# pr0board_key.net
KiCad netlist of a schematic drawn in EAGLE
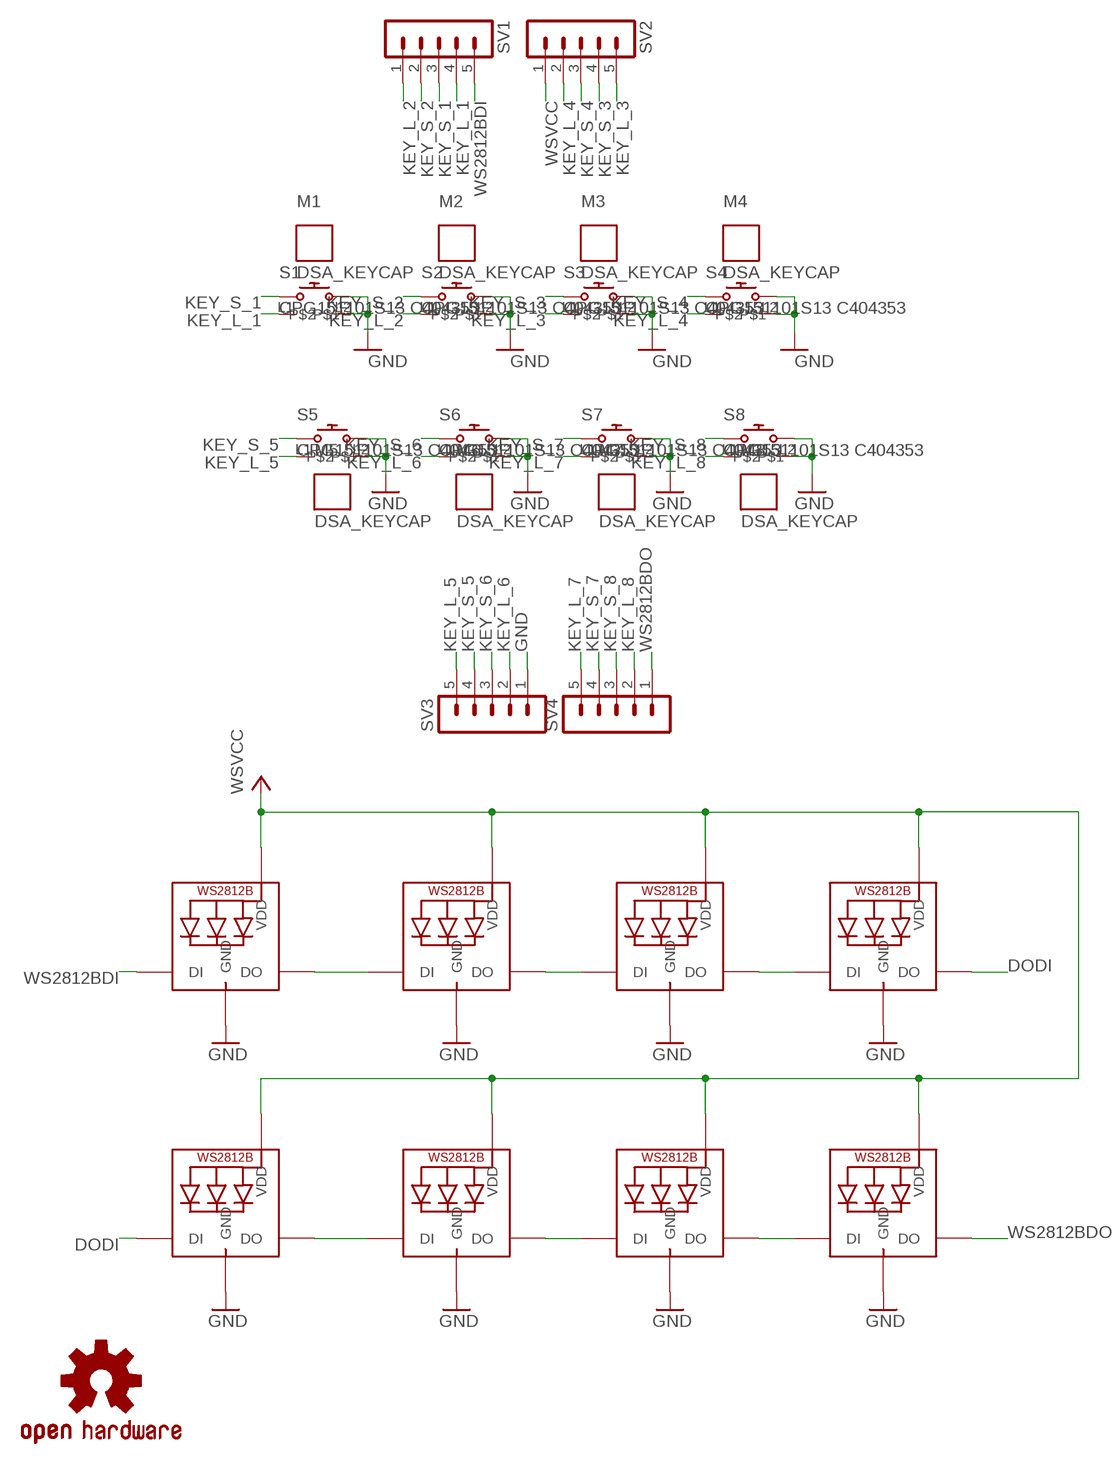
[diagram p0: schematic, sheet 1]

(export (version "E")
  (design (tool "Eeschema 10.0.6"))
  (components
    (comp (ref "LED1")
      (value "WS2812B3535")
      (footprint "eagle-import:LED3535")
      (libsource (lib "eagle-import") (part "WS2812B3535"))
    )
    (comp (ref "LED2")
      (value "WS2812B3535")
      (footprint "eagle-import:LED3535")
      (libsource (lib "eagle-import") (part "WS2812B3535"))
    )
    (comp (ref "LED3")
      (value "WS2812B3535")
      (footprint "eagle-import:LED3535")
      (libsource (lib "eagle-import") (part "WS2812B3535"))
    )
    (comp (ref "LED4")
      (value "WS2812B3535")
      (footprint "eagle-import:LED3535")
      (libsource (lib "eagle-import") (part "WS2812B3535"))
    )
    (comp (ref "LED5")
      (value "WS2812B3535")
      (footprint "eagle-import:LED3535")
      (libsource (lib "eagle-import") (part "WS2812B3535"))
    )
    (comp (ref "LED6")
      (value "WS2812B3535")
      (footprint "eagle-import:LED3535")
      (libsource (lib "eagle-import") (part "WS2812B3535"))
    )
    (comp (ref "LED7")
      (value "WS2812B3535")
      (footprint "eagle-import:LED3535")
      (libsource (lib "eagle-import") (part "WS2812B3535"))
    )
    (comp (ref "LED8")
      (value "WS2812B3535")
      (footprint "eagle-import:LED3535")
      (libsource (lib "eagle-import") (part "WS2812B3535"))
    )
    (comp (ref "M1")
      (value "DSA_KEYCAP")
      (footprint "eagle-import:DSA_KEYCAP")
      (libsource (lib "eagle-import") (part "DSA_KEYCAP"))
    )
    (comp (ref "M2")
      (value "DSA_KEYCAP")
      (footprint "eagle-import:DSA_KEYCAP")
      (libsource (lib "eagle-import") (part "DSA_KEYCAP"))
    )
    (comp (ref "M3")
      (value "DSA_KEYCAP")
      (footprint "eagle-import:DSA_KEYCAP")
      (libsource (lib "eagle-import") (part "DSA_KEYCAP"))
    )
    (comp (ref "M4")
      (value "DSA_KEYCAP")
      (footprint "eagle-import:DSA_KEYCAP")
      (libsource (lib "eagle-import") (part "DSA_KEYCAP"))
    )
    (comp (ref "M5")
      (value "DSA_KEYCAP")
      (footprint "eagle-import:DSA_KEYCAP")
      (libsource (lib "eagle-import") (part "DSA_KEYCAP"))
    )
    (comp (ref "M6")
      (value "DSA_KEYCAP")
      (footprint "eagle-import:DSA_KEYCAP")
      (libsource (lib "eagle-import") (part "DSA_KEYCAP"))
    )
    (comp (ref "M7")
      (value "DSA_KEYCAP")
      (footprint "eagle-import:DSA_KEYCAP")
      (libsource (lib "eagle-import") (part "DSA_KEYCAP"))
    )
    (comp (ref "M8")
      (value "DSA_KEYCAP")
      (footprint "eagle-import:DSA_KEYCAP")
      (libsource (lib "eagle-import") (part "DSA_KEYCAP"))
    )
    (comp (ref "S1")
      (value "CPG151101S13 C404353")
      (footprint "eagle-import:CHERRY_MX_LED")
      (libsource (lib "eagle-import") (part "CHERRY_MX_LED"))
    )
    (comp (ref "S2")
      (value "CPG151101S13 C404353")
      (footprint "eagle-import:CHERRY_MX_LED")
      (libsource (lib "eagle-import") (part "CHERRY_MX_LED"))
    )
    (comp (ref "S3")
      (value "CPG151101S13 C404353")
      (footprint "eagle-import:CHERRY_MX_LED")
      (libsource (lib "eagle-import") (part "CHERRY_MX_LED"))
    )
    (comp (ref "S4")
      (value "CPG151101S13 C404353")
      (footprint "eagle-import:CHERRY_MX_LED")
      (libsource (lib "eagle-import") (part "CHERRY_MX_LED"))
    )
    (comp (ref "S5")
      (value "CPG151101S13 C404353")
      (footprint "eagle-import:CHERRY_MX_LED")
      (libsource (lib "eagle-import") (part "CHERRY_MX_LED"))
    )
    (comp (ref "S6")
      (value "CPG151101S13 C404353")
      (footprint "eagle-import:CHERRY_MX_LED")
      (libsource (lib "eagle-import") (part "CHERRY_MX_LED"))
    )
    (comp (ref "S7")
      (value "CPG151101S13 C404353")
      (footprint "eagle-import:CHERRY_MX_LED")
      (libsource (lib "eagle-import") (part "CHERRY_MX_LED"))
    )
    (comp (ref "S8")
      (value "CPG151101S13 C404353")
      (footprint "eagle-import:CHERRY_MX_LED")
      (libsource (lib "eagle-import") (part "CHERRY_MX_LED"))
    )
    (comp (ref "SV1")
      (value "MA05-1")
      (footprint "eagle-import:MA05-1")
      (libsource (lib "eagle-import") (part "MA05-1"))
    )
    (comp (ref "SV2")
      (value "MA05-1")
      (footprint "eagle-import:MA05-1")
      (libsource (lib "eagle-import") (part "MA05-1"))
    )
    (comp (ref "SV3")
      (value "MA05-1")
      (footprint "eagle-import:MA05-1")
      (libsource (lib "eagle-import") (part "MA05-1"))
    )
    (comp (ref "SV4")
      (value "MA05-1")
      (footprint "eagle-import:MA05-1")
      (libsource (lib "eagle-import") (part "MA05-1"))
    )
    (comp (ref "U$1")
      (value "OSHW-LOGOS")
      (footprint "eagle-import:OSHW-LOGO-S")
      (libsource (lib "eagle-import") (part "OSHW-LOGOS"))
    )
  )
  (nets
    (net (code "1") (name "/DODI") (class "Default")
      (node (ref "LED4") (pin "2") (pinfunction "DO_2") (pintype "output"))
      (node (ref "LED5") (pin "4") (pinfunction "DI_4") (pintype "input"))
    )
    (net (code "2") (name "/KEY_L_1") (class "Default")
      (node (ref "S1") (pin "L1") (pinfunction "P$1_L1") (pintype "bidirectional"))
      (node (ref "SV1") (pin "4") (pinfunction "4_4") (pintype "passive"))
    )
    (net (code "3") (name "/KEY_L_2") (class "Default")
      (node (ref "S2") (pin "L1") (pinfunction "P$1_L1") (pintype "bidirectional"))
      (node (ref "SV1") (pin "1") (pinfunction "1_1") (pintype "passive"))
    )
    (net (code "4") (name "/KEY_L_3") (class "Default")
      (node (ref "S3") (pin "L1") (pinfunction "P$1_L1") (pintype "bidirectional"))
      (node (ref "SV2") (pin "5") (pinfunction "5_5") (pintype "passive"))
    )
    (net (code "5") (name "/KEY_L_4") (class "Default")
      (node (ref "S4") (pin "L1") (pinfunction "P$1_L1") (pintype "bidirectional"))
      (node (ref "SV2") (pin "2") (pinfunction "2_2") (pintype "passive"))
    )
    (net (code "6") (name "/KEY_L_5") (class "Default")
      (node (ref "S5") (pin "L1") (pinfunction "P$1_L1") (pintype "bidirectional"))
      (node (ref "SV3") (pin "5") (pinfunction "5_5") (pintype "passive"))
    )
    (net (code "7") (name "/KEY_L_6") (class "Default")
      (node (ref "S6") (pin "L1") (pinfunction "P$1_L1") (pintype "bidirectional"))
      (node (ref "SV3") (pin "2") (pinfunction "2_2") (pintype "passive"))
    )
    (net (code "8") (name "/KEY_L_7") (class "Default")
      (node (ref "S7") (pin "L1") (pinfunction "P$1_L1") (pintype "bidirectional"))
      (node (ref "SV4") (pin "5") (pinfunction "5_5") (pintype "passive"))
    )
    (net (code "9") (name "/KEY_L_8") (class "Default")
      (node (ref "S8") (pin "L1") (pinfunction "P$1_L1") (pintype "bidirectional"))
      (node (ref "SV4") (pin "2") (pinfunction "2_2") (pintype "passive"))
    )
    (net (code "10") (name "/KEY_S_1") (class "Default")
      (node (ref "S1") (pin "S1") (pinfunction "1_S1") (pintype "passive"))
      (node (ref "SV1") (pin "3") (pinfunction "3_3") (pintype "passive"))
    )
    (net (code "11") (name "/KEY_S_2") (class "Default")
      (node (ref "S2") (pin "S1") (pinfunction "1_S1") (pintype "passive"))
      (node (ref "SV1") (pin "2") (pinfunction "2_2") (pintype "passive"))
    )
    (net (code "12") (name "/KEY_S_3") (class "Default")
      (node (ref "S3") (pin "S1") (pinfunction "1_S1") (pintype "passive"))
      (node (ref "SV2") (pin "4") (pinfunction "4_4") (pintype "passive"))
    )
    (net (code "13") (name "/KEY_S_4") (class "Default")
      (node (ref "S4") (pin "S1") (pinfunction "1_S1") (pintype "passive"))
      (node (ref "SV2") (pin "3") (pinfunction "3_3") (pintype "passive"))
    )
    (net (code "14") (name "/KEY_S_5") (class "Default")
      (node (ref "S5") (pin "S1") (pinfunction "1_S1") (pintype "passive"))
      (node (ref "SV3") (pin "4") (pinfunction "4_4") (pintype "passive"))
    )
    (net (code "15") (name "/KEY_S_6") (class "Default")
      (node (ref "S6") (pin "S1") (pinfunction "1_S1") (pintype "passive"))
      (node (ref "SV3") (pin "3") (pinfunction "3_3") (pintype "passive"))
    )
    (net (code "16") (name "/KEY_S_7") (class "Default")
      (node (ref "S7") (pin "S1") (pinfunction "1_S1") (pintype "passive"))
      (node (ref "SV4") (pin "4") (pinfunction "4_4") (pintype "passive"))
    )
    (net (code "17") (name "/KEY_S_8") (class "Default")
      (node (ref "S8") (pin "S1") (pinfunction "1_S1") (pintype "passive"))
      (node (ref "SV4") (pin "3") (pinfunction "3_3") (pintype "passive"))
    )
    (net (code "18") (name "/WS2812BDI") (class "Default")
      (node (ref "LED1") (pin "4") (pinfunction "DI_4") (pintype "input"))
      (node (ref "SV1") (pin "5") (pinfunction "5_5") (pintype "passive"))
    )
    (net (code "19") (name "/WS2812BDO") (class "Default")
      (node (ref "LED8") (pin "2") (pinfunction "DO_2") (pintype "output"))
      (node (ref "SV4") (pin "1") (pinfunction "1_1") (pintype "passive"))
    )
    (net (code "20") (name "GND") (class "Default")
      (node (ref "LED1") (pin "3") (pinfunction "GND_3") (pintype "power_in"))
      (node (ref "LED2") (pin "3") (pinfunction "GND_3") (pintype "power_in"))
      (node (ref "LED3") (pin "3") (pinfunction "GND_3") (pintype "power_in"))
      (node (ref "LED4") (pin "3") (pinfunction "GND_3") (pintype "power_in"))
      (node (ref "LED5") (pin "3") (pinfunction "GND_3") (pintype "power_in"))
      (node (ref "LED6") (pin "3") (pinfunction "GND_3") (pintype "power_in"))
      (node (ref "LED7") (pin "3") (pinfunction "GND_3") (pintype "power_in"))
      (node (ref "LED8") (pin "3") (pinfunction "GND_3") (pintype "power_in"))
      (node (ref "S1") (pin "L2") (pinfunction "P$2_L2") (pintype "bidirectional"))
      (node (ref "S1") (pin "S2") (pinfunction "2_S2") (pintype "passive"))
      (node (ref "S2") (pin "L2") (pinfunction "P$2_L2") (pintype "bidirectional"))
      (node (ref "S2") (pin "S2") (pinfunction "2_S2") (pintype "passive"))
      (node (ref "S3") (pin "L2") (pinfunction "P$2_L2") (pintype "bidirectional"))
      (node (ref "S3") (pin "S2") (pinfunction "2_S2") (pintype "passive"))
      (node (ref "S4") (pin "L2") (pinfunction "P$2_L2") (pintype "bidirectional"))
      (node (ref "S4") (pin "S2") (pinfunction "2_S2") (pintype "passive"))
      (node (ref "S5") (pin "L2") (pinfunction "P$2_L2") (pintype "bidirectional"))
      (node (ref "S5") (pin "S2") (pinfunction "2_S2") (pintype "passive"))
      (node (ref "S6") (pin "L2") (pinfunction "P$2_L2") (pintype "bidirectional"))
      (node (ref "S6") (pin "S2") (pinfunction "2_S2") (pintype "passive"))
      (node (ref "S7") (pin "L2") (pinfunction "P$2_L2") (pintype "bidirectional"))
      (node (ref "S7") (pin "S2") (pinfunction "2_S2") (pintype "passive"))
      (node (ref "S8") (pin "L2") (pinfunction "P$2_L2") (pintype "bidirectional"))
      (node (ref "S8") (pin "S2") (pinfunction "2_S2") (pintype "passive"))
      (node (ref "SV3") (pin "1") (pinfunction "1_1") (pintype "passive"))
    )
    (net (code "21") (name "Net-(LED1-DO)") (class "Default")
      (node (ref "LED1") (pin "2") (pinfunction "DO_2") (pintype "output"))
      (node (ref "LED2") (pin "4") (pinfunction "DI_4") (pintype "input"))
    )
    (net (code "22") (name "Net-(LED2-DO)") (class "Default")
      (node (ref "LED2") (pin "2") (pinfunction "DO_2") (pintype "output"))
      (node (ref "LED3") (pin "4") (pinfunction "DI_4") (pintype "input"))
    )
    (net (code "23") (name "Net-(LED3-DO)") (class "Default")
      (node (ref "LED3") (pin "2") (pinfunction "DO_2") (pintype "output"))
      (node (ref "LED4") (pin "4") (pinfunction "DI_4") (pintype "input"))
    )
    (net (code "24") (name "Net-(LED5-DO)") (class "Default")
      (node (ref "LED5") (pin "2") (pinfunction "DO_2") (pintype "output"))
      (node (ref "LED6") (pin "4") (pinfunction "DI_4") (pintype "input"))
    )
    (net (code "25") (name "Net-(LED6-DO)") (class "Default")
      (node (ref "LED6") (pin "2") (pinfunction "DO_2") (pintype "output"))
      (node (ref "LED7") (pin "4") (pinfunction "DI_4") (pintype "input"))
    )
    (net (code "26") (name "Net-(LED7-DO)") (class "Default")
      (node (ref "LED7") (pin "2") (pinfunction "DO_2") (pintype "output"))
      (node (ref "LED8") (pin "4") (pinfunction "DI_4") (pintype "input"))
    )
    (net (code "27") (name "WSVCC") (class "Default")
      (node (ref "LED1") (pin "1") (pinfunction "VDD_1") (pintype "power_in"))
      (node (ref "LED2") (pin "1") (pinfunction "VDD_1") (pintype "power_in"))
      (node (ref "LED3") (pin "1") (pinfunction "VDD_1") (pintype "power_in"))
      (node (ref "LED4") (pin "1") (pinfunction "VDD_1") (pintype "power_in"))
      (node (ref "LED5") (pin "1") (pinfunction "VDD_1") (pintype "power_in"))
      (node (ref "LED6") (pin "1") (pinfunction "VDD_1") (pintype "power_in"))
      (node (ref "LED7") (pin "1") (pinfunction "VDD_1") (pintype "power_in"))
      (node (ref "LED8") (pin "1") (pinfunction "VDD_1") (pintype "power_in"))
      (node (ref "SV2") (pin "1") (pinfunction "1_1") (pintype "passive"))
    )
  )
)
